# Sensors.net
KiCad netlist of a schematic drawn in Altium Designer
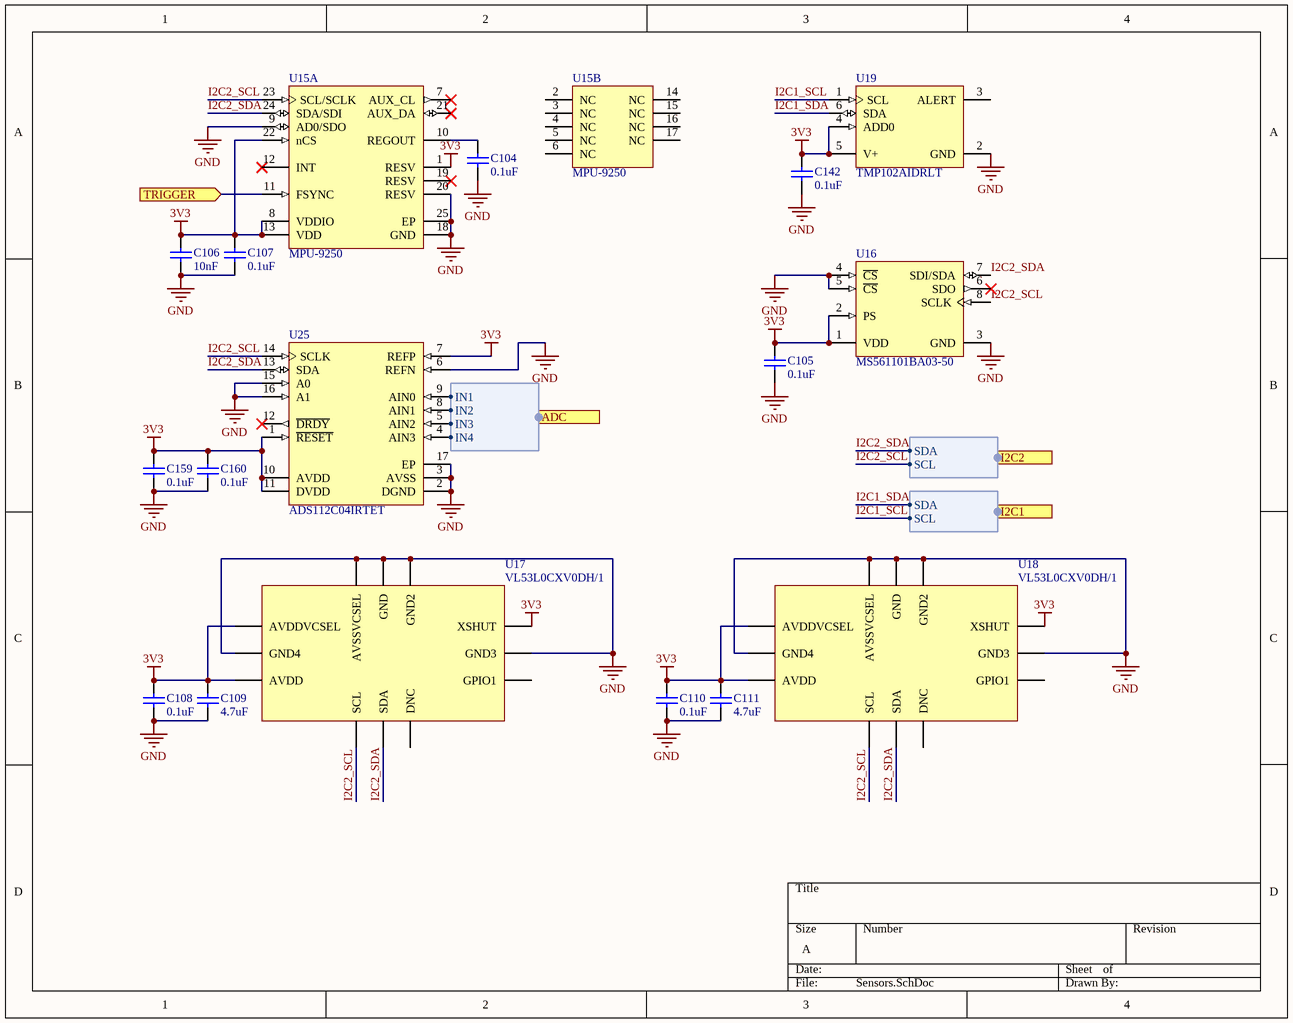
[diagram p0: Sensors.SchDoc]

(export (version "E")
  (design (tool "Eeschema 10.0.6"))
  (components
    (comp (ref "C104")
      (value "0.1uF")
      (footprint "C0402[1005X55]")
      (description "0.1uF 6.3V 10% 0402 (1005 Metric)")
      (fields (field (name "PARTNUMBER") "GRM155R70J104KA01D") (field (name "MANUFACTURER") "Murata"))
      (libsource (lib "Capacitors") (part "CAP_0.1uF_6.3V_0402_10%"))
    )
    (comp (ref "C105")
      (value "0.1uF")
      (footprint "C0402[1005X55]")
      (description "0.1uF 6.3V 10% 0402 (1005 Metric)")
      (fields (field (name "PARTNUMBER") "GRM155R70J104KA01D") (field (name "MANUFACTURER") "Murata"))
      (libsource (lib "Capacitors") (part "CAP_0.1uF_6.3V_0402_10%"))
    )
    (comp (ref "C106")
      (value "10nF")
      (footprint "C0402[1005X55]")
      (description "10nF 50V 10% 0402 (1005 Metric)")
      (fields (field (name "PARTNUMBER") "GCM155R71H103KA55D") (field (name "MANUFACTURER") "Murata"))
      (libsource (lib "Capacitors") (part "CAP_10nF_50V_0402_10%"))
    )
    (comp (ref "C107")
      (value "0.1uF")
      (footprint "C0402[1005X55]")
      (description "0.1uF 6.3V 10% 0402 (1005 Metric)")
      (fields (field (name "PARTNUMBER") "GRM155R70J104KA01D") (field (name "MANUFACTURER") "Murata"))
      (libsource (lib "Capacitors") (part "CAP_0.1uF_6.3V_0402_10%"))
    )
    (comp (ref "C108")
      (value "0.1uF")
      (footprint "C0402[1005X55]")
      (description "0.1uF 6.3V 10% 0402 (1005 Metric)")
      (fields (field (name "PARTNUMBER") "GRM155R70J104KA01D") (field (name "MANUFACTURER") "Murata"))
      (libsource (lib "Capacitors") (part "CAP_0.1uF_6.3V_0402_10%"))
    )
    (comp (ref "C109")
      (value "4.7uF")
      (footprint "C0402[1005X55]")
      (description "4.7uF 6.3V 20% 0402 (1005 Metric)")
      (fields (field (name "PARTNUMBER") "GRM155R60J475ME47D") (field (name "MANUFACTURER") "Murata"))
      (libsource (lib "Capacitors") (part "CAP_4.7uF_6.3V_0402_20%"))
    )
    (comp (ref "C110")
      (value "0.1uF")
      (footprint "C0402[1005X55]")
      (description "0.1uF 6.3V 10% 0402 (1005 Metric)")
      (fields (field (name "PARTNUMBER") "GRM155R70J104KA01D") (field (name "MANUFACTURER") "Murata"))
      (libsource (lib "Capacitors") (part "CAP_0.1uF_6.3V_0402_10%"))
    )
    (comp (ref "C111")
      (value "4.7uF")
      (footprint "C0402[1005X55]")
      (description "4.7uF 6.3V 20% 0402 (1005 Metric)")
      (fields (field (name "PARTNUMBER") "GRM155R60J475ME47D") (field (name "MANUFACTURER") "Murata"))
      (libsource (lib "Capacitors") (part "CAP_4.7uF_6.3V_0402_20%"))
    )
    (comp (ref "C142")
      (value "0.1uF")
      (footprint "C0402[1005X55]")
      (description "0.1uF 6.3V 10% 0402 (1005 Metric)")
      (fields (field (name "PARTNUMBER") "GRM155R70J104KA01D") (field (name "MANUFACTURER") "Murata"))
      (libsource (lib "Capacitors") (part "CAP_0.1uF_6.3V_0402_10%"))
    )
    (comp (ref "C159")
      (value "0.1uF")
      (footprint "C0402[1005X55]")
      (description "0.1uF 6.3V 10% 0402 (1005 Metric)")
      (fields (field (name "PARTNUMBER") "GRM155R70J104KA01D") (field (name "MANUFACTURER") "Murata"))
      (libsource (lib "Capacitors") (part "CAP_0.1uF_6.3V_0402_10%"))
    )
    (comp (ref "C160")
      (value "0.1uF")
      (footprint "C0402[1005X55]")
      (description "0.1uF 6.3V 10% 0402 (1005 Metric)")
      (fields (field (name "PARTNUMBER") "GRM155R70J104KA01D") (field (name "MANUFACTURER") "Murata"))
      (libsource (lib "Capacitors") (part "CAP_0.1uF_6.3V_0402_10%"))
    )
    (comp (ref "U15")
      (value "MPU-9250")
      (footprint "QFN-24 (0.4MM)")
      (fields (field (name "MANUFACTURER") "Invensense"))
      (libsource (lib "ICs") (part "MPU-9250"))
    )
    (comp (ref "U16")
      (value "MS561101BA03-50")
      (footprint "QFN-8 (5x3MM)")
      (description "BAROMETRIC PRESSURE SENSOR")
      (fields (field (name "MANUFACTURER") "TE Connectivity Measurement Specialties"))
      (libsource (lib "ICs") (part "MS561101BA03-50"))
    )
    (comp (ref "U17")
      (value "VL53L0CXV0DH/1")
      (footprint "LGA-12")
      (description "Optical Sensor Modules Time-of-Flight (ToF) ranging sensor")
      (fields (field (name "MANUFACTURER") "STMicroelectronics"))
      (libsource (lib "ICs") (part "VL53L0CXV0DH/1"))
    )
    (comp (ref "U18")
      (value "VL53L0CXV0DH/1")
      (footprint "LGA-12")
      (description "Optical Sensor Modules Time-of-Flight (ToF) ranging sensor")
      (fields (field (name "MANUFACTURER") "STMicroelectronics"))
      (libsource (lib "ICs") (part "VL53L0CXV0DH/1"))
    )
    (comp (ref "U19")
      (value "TMP102AIDRLT")
      (footprint "SOT-563")
      (description "SENSOR DIGITAL -40C-125C SOT563")
      (fields (field (name "MANUFACTURER") "Texas Instruments"))
      (libsource (lib "ICs") (part "TMP102AIDRLT"))
    )
    (comp (ref "U25")
      (value "ADS112C04IRTET")
      (footprint "QFN-16")
      (description "IC ADC 16BIT I2C 1KSPS 16WQFN")
      (fields (field (name "MANUFACTURER") "Texas Instruments"))
      (libsource (lib "ICs") (part "ADS112C04IRTET"))
    )
  )
  (nets
    (net (code "3") (name "/I2C1_SCL") (class "Default")
      (node (ref "U19") (pin "1") (pinfunction "SCL_1") (pintype "input"))
    )
    (net (code "4") (name "/I2C1_SDA") (class "Default")
      (node (ref "U19") (pin "6") (pinfunction "SDA_6") (pintype "bidirectional"))
    )
    (net (code "5") (name "/I2C2_SCL") (class "Default")
      (node (ref "U15") (pin "23") (pinfunction "SCL/SCLK_23") (pintype "input"))
      (node (ref "U16") (pin "8") (pinfunction "SCLK_8") (pintype "input"))
      (node (ref "U17") (pin "10") (pinfunction "SCL_10") (pintype "passive"))
      (node (ref "U18") (pin "10") (pinfunction "SCL_10") (pintype "passive"))
      (node (ref "U25") (pin "14") (pinfunction "SCLK_14") (pintype "input"))
    )
    (net (code "6") (name "/I2C2_SDA") (class "Default")
      (node (ref "U15") (pin "24") (pinfunction "SDA/SDI_24") (pintype "bidirectional"))
      (node (ref "U16") (pin "7") (pinfunction "SDI/SDA_7") (pintype "bidirectional"))
      (node (ref "U17") (pin "9") (pinfunction "SDA_9") (pintype "passive"))
      (node (ref "U18") (pin "9") (pinfunction "SDA_9") (pintype "passive"))
      (node (ref "U25") (pin "13") (pinfunction "SDA_13") (pintype "bidirectional"))
    )
    (net (code "7") (name "/IN1") (class "Default")
      (node (ref "U25") (pin "9") (pinfunction "AIN0_9") (pintype "input"))
    )
    (net (code "8") (name "/IN2") (class "Default")
      (node (ref "U25") (pin "8") (pinfunction "AIN1_8") (pintype "input"))
    )
    (net (code "9") (name "/IN3") (class "Default")
      (node (ref "U25") (pin "5") (pinfunction "AIN2_5") (pintype "input"))
    )
    (net (code "10") (name "/IN4") (class "Default")
      (node (ref "U25") (pin "4") (pinfunction "AIN3_4") (pintype "input"))
    )
    (net (code "11") (name "/TRIGGER") (class "Default")
      (node (ref "U15") (pin "11") (pinfunction "FSYNC_11") (pintype "input"))
    )
    (net (code "14") (name "3V3") (class "Default")
      (node (ref "C105") (pin "2") (pinfunction "2_2") (pintype "passive"))
      (node (ref "C106") (pin "2") (pinfunction "2_2") (pintype "passive"))
      (node (ref "C107") (pin "2") (pinfunction "2_2") (pintype "passive"))
      (node (ref "C108") (pin "2") (pinfunction "2_2") (pintype "passive"))
      (node (ref "C109") (pin "2") (pinfunction "2_2") (pintype "passive"))
      (node (ref "C110") (pin "2") (pinfunction "2_2") (pintype "passive"))
      (node (ref "C111") (pin "2") (pinfunction "2_2") (pintype "passive"))
      (node (ref "C142") (pin "2") (pinfunction "2_2") (pintype "passive"))
      (node (ref "C159") (pin "2") (pinfunction "2_2") (pintype "passive"))
      (node (ref "C160") (pin "2") (pinfunction "2_2") (pintype "passive"))
      (node (ref "U15") (pin "1") (pinfunction "RESV_1") (pintype "power_in"))
      (node (ref "U15") (pin "13") (pinfunction "VDD_13") (pintype "power_in"))
      (node (ref "U15") (pin "22") (pinfunction "nCS_22") (pintype "input"))
      (node (ref "U15") (pin "8") (pinfunction "VDDIO_8") (pintype "power_in"))
      (node (ref "U16") (pin "1") (pinfunction "VDD_1") (pintype "power_in"))
      (node (ref "U16") (pin "2") (pinfunction "PS_2") (pintype "input"))
      (node (ref "U17") (pin "1") (pinfunction "AVDDVCSEL_1") (pintype "passive"))
      (node (ref "U17") (pin "11") (pinfunction "AVDD_11") (pintype "passive"))
      (node (ref "U17") (pin "5") (pinfunction "XSHUT_5") (pintype "passive"))
      (node (ref "U18") (pin "1") (pinfunction "AVDDVCSEL_1") (pintype "passive"))
      (node (ref "U18") (pin "11") (pinfunction "AVDD_11") (pintype "passive"))
      (node (ref "U18") (pin "5") (pinfunction "XSHUT_5") (pintype "passive"))
      (node (ref "U19") (pin "4") (pinfunction "ADD0_4") (pintype "input"))
      (node (ref "U19") (pin "5") (pinfunction "V+_5") (pintype "power_in"))
      (node (ref "U25") (pin "1") (pinfunction "~{RESET}_1") (pintype "input"))
      (node (ref "U25") (pin "10") (pinfunction "AVDD_10") (pintype "power_in"))
      (node (ref "U25") (pin "11") (pinfunction "DVDD_11") (pintype "power_in"))
      (node (ref "U25") (pin "7") (pinfunction "REFP_7") (pintype "input"))
    )
    (net (code "15") (name "GND") (class "Default")
      (node (ref "C104") (pin "1") (pinfunction "1_1") (pintype "passive"))
      (node (ref "C105") (pin "1") (pinfunction "1_1") (pintype "passive"))
      (node (ref "C106") (pin "1") (pinfunction "1_1") (pintype "passive"))
      (node (ref "C107") (pin "1") (pinfunction "1_1") (pintype "passive"))
      (node (ref "C108") (pin "1") (pinfunction "1_1") (pintype "passive"))
      (node (ref "C109") (pin "1") (pinfunction "1_1") (pintype "passive"))
      (node (ref "C110") (pin "1") (pinfunction "1_1") (pintype "passive"))
      (node (ref "C111") (pin "1") (pinfunction "1_1") (pintype "passive"))
      (node (ref "C142") (pin "1") (pinfunction "1_1") (pintype "passive"))
      (node (ref "C159") (pin "1") (pinfunction "1_1") (pintype "passive"))
      (node (ref "C160") (pin "1") (pinfunction "1_1") (pintype "passive"))
      (node (ref "U15") (pin "18") (pinfunction "GND_18") (pintype "power_in"))
      (node (ref "U15") (pin "20") (pinfunction "RESV_20") (pintype "power_in"))
      (node (ref "U15") (pin "25") (pinfunction "EP_25") (pintype "passive"))
      (node (ref "U15") (pin "9") (pinfunction "AD0/SDO_9") (pintype "bidirectional"))
      (node (ref "U16") (pin "3") (pinfunction "GND_3") (pintype "power_in"))
      (node (ref "U16") (pin "4") (pinfunction "~{CS}_4") (pintype "input"))
      (node (ref "U16") (pin "5") (pinfunction "~{CS}_5") (pintype "input"))
      (node (ref "U17") (pin "12") (pinfunction "GND4_12") (pintype "passive"))
      (node (ref "U17") (pin "2") (pinfunction "AVSSVCSEL_2") (pintype "passive"))
      (node (ref "U17") (pin "3") (pinfunction "GND_3") (pintype "passive"))
      (node (ref "U17") (pin "4") (pinfunction "GND2_4") (pintype "passive"))
      (node (ref "U17") (pin "6") (pinfunction "GND3_6") (pintype "passive"))
      (node (ref "U18") (pin "12") (pinfunction "GND4_12") (pintype "passive"))
      (node (ref "U18") (pin "2") (pinfunction "AVSSVCSEL_2") (pintype "passive"))
      (node (ref "U18") (pin "3") (pinfunction "GND_3") (pintype "passive"))
      (node (ref "U18") (pin "4") (pinfunction "GND2_4") (pintype "passive"))
      (node (ref "U18") (pin "6") (pinfunction "GND3_6") (pintype "passive"))
      (node (ref "U19") (pin "2") (pinfunction "GND_2") (pintype "power_in"))
      (node (ref "U25") (pin "15") (pinfunction "A0_15") (pintype "input"))
      (node (ref "U25") (pin "16") (pinfunction "A1_16") (pintype "input"))
      (node (ref "U25") (pin "17") (pinfunction "EP_17") (pintype "power_in"))
      (node (ref "U25") (pin "2") (pinfunction "DGND_2") (pintype "power_in"))
      (node (ref "U25") (pin "3") (pinfunction "AVSS_3") (pintype "power_in"))
      (node (ref "U25") (pin "6") (pinfunction "REFN_6") (pintype "input"))
    )
    (net (code "16") (name "Net-(U15A-REGOUT)") (class "Default")
      (node (ref "C104") (pin "2") (pinfunction "2_2") (pintype "passive"))
      (node (ref "U15") (pin "10") (pinfunction "REGOUT_10") (pintype "passive"))
    )
    (net (code "17") (name "unconnected-(U15A-AUX_CL-Pad7)") (class "Default")
      (node (ref "U15") (pin "7") (pinfunction "AUX_CL_7") (pintype "output+no_connect"))
    )
    (net (code "18") (name "unconnected-(U15A-AUX_DA-Pad21)") (class "Default")
      (node (ref "U15") (pin "21") (pinfunction "AUX_DA_21") (pintype "bidirectional+no_connect"))
    )
    (net (code "19") (name "unconnected-(U15A-INT-Pad12)") (class "Default")
      (node (ref "U15") (pin "12") (pinfunction "INT_12") (pintype "tri_state+no_connect"))
    )
    (net (code "20") (name "unconnected-(U15A-RESV-Pad19)") (class "Default")
      (node (ref "U15") (pin "19") (pinfunction "RESV_19") (pintype "passive+no_connect"))
    )
    (net (code "21") (name "unconnected-(U15B-NC-Pad2)") (class "Default")
      (node (ref "U15") (pin "2") (pinfunction "NC_2") (pintype "passive"))
    )
    (net (code "22") (name "unconnected-(U15B-NC-Pad3)") (class "Default")
      (node (ref "U15") (pin "3") (pinfunction "NC_3") (pintype "passive"))
    )
    (net (code "23") (name "unconnected-(U15B-NC-Pad4)") (class "Default")
      (node (ref "U15") (pin "4") (pinfunction "NC_4") (pintype "passive"))
    )
    (net (code "24") (name "unconnected-(U15B-NC-Pad5)") (class "Default")
      (node (ref "U15") (pin "5") (pinfunction "NC_5") (pintype "passive"))
    )
    (net (code "25") (name "unconnected-(U15B-NC-Pad6)") (class "Default")
      (node (ref "U15") (pin "6") (pinfunction "NC_6") (pintype "passive"))
    )
    (net (code "26") (name "unconnected-(U15B-NC-Pad14)") (class "Default")
      (node (ref "U15") (pin "14") (pinfunction "NC_14") (pintype "passive"))
    )
    (net (code "27") (name "unconnected-(U15B-NC-Pad15)") (class "Default")
      (node (ref "U15") (pin "15") (pinfunction "NC_15") (pintype "passive"))
    )
    (net (code "28") (name "unconnected-(U15B-NC-Pad16)") (class "Default")
      (node (ref "U15") (pin "16") (pinfunction "NC_16") (pintype "passive"))
    )
    (net (code "29") (name "unconnected-(U15B-NC-Pad17)") (class "Default")
      (node (ref "U15") (pin "17") (pinfunction "NC_17") (pintype "passive"))
    )
    (net (code "30") (name "unconnected-(U16-SDO-Pad6)") (class "Default")
      (node (ref "U16") (pin "6") (pinfunction "SDO_6") (pintype "output+no_connect"))
    )
    (net (code "31") (name "unconnected-(U17-DNC-Pad8)") (class "Default")
      (node (ref "U17") (pin "8") (pinfunction "DNC_8") (pintype "passive"))
    )
    (net (code "32") (name "unconnected-(U17-GPIO1-Pad7)") (class "Default")
      (node (ref "U17") (pin "7") (pinfunction "GPIO1_7") (pintype "passive"))
    )
    (net (code "33") (name "unconnected-(U18-DNC-Pad8)") (class "Default")
      (node (ref "U18") (pin "8") (pinfunction "DNC_8") (pintype "passive"))
    )
    (net (code "34") (name "unconnected-(U18-GPIO1-Pad7)") (class "Default")
      (node (ref "U18") (pin "7") (pinfunction "GPIO1_7") (pintype "passive"))
    )
    (net (code "35") (name "unconnected-(U19-ALERT-Pad3)") (class "Default")
      (node (ref "U19") (pin "3") (pinfunction "ALERT_3") (pintype "open_collector"))
    )
    (net (code "36") (name "unconnected-(U25-~{DRDY}-Pad12)") (class "Default")
      (node (ref "U25") (pin "12") (pinfunction "~{DRDY}_12") (pintype "output+no_connect"))
    )
  )
)
